# PDM-S01-V00-TempSensing.net
KiCad netlist of a schematic drawn in Altium Designer
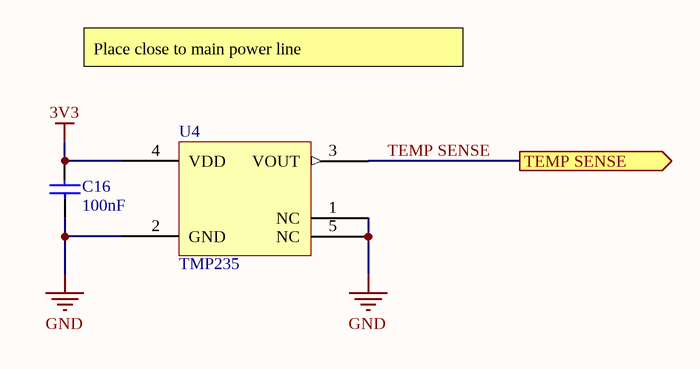
[diagram p0: PDM-S01-V00-TempSensing.SchDoc]

(export (version "E")
  (design (tool "Eeschema 10.0.6"))
  (components
    (comp (ref "C16")
      (value "100nF")
      (footprint "Cap_Ceramic_0603")
      (description "Capacitor, Ceramic, SMD, 100nF, 50V, 5%, X7R, 0603")
      (libsource (lib "StandardCapacitors") (part "100nF 50V 5% X7R 0603"))
    )
    (comp (ref "U4")
      (value "TMP235")
      (footprint "SC70")
      (description "TMP235, Low-Power, High-Accuracy Analog Output Temperature Sensor")
      (libsource (lib "PDM-CARD-SCHLib-V00") (part "TMP235"))
    )
  )
  (nets
    (net (code "1") (name "/TEMP SENSE") (class "Default")
      (node (ref "U4") (pin "3") (pinfunction "VOUT_3") (pintype "output"))
    )
    (net (code "2") (name "3V3") (class "Default")
      (node (ref "C16") (pin "2") (pinfunction "2_2") (pintype "passive"))
      (node (ref "U4") (pin "4") (pinfunction "VDD_4") (pintype "passive"))
    )
    (net (code "3") (name "GND") (class "Default")
      (node (ref "C16") (pin "1") (pinfunction "1_1") (pintype "passive"))
      (node (ref "U4") (pin "1") (pinfunction "NC_1") (pintype "passive"))
      (node (ref "U4") (pin "2") (pinfunction "GND_2") (pintype "passive"))
      (node (ref "U4") (pin "5") (pinfunction "NC_5") (pintype "passive"))
    )
  )
)
